# Power.net
KiCad netlist of a schematic drawn in Altium Designer
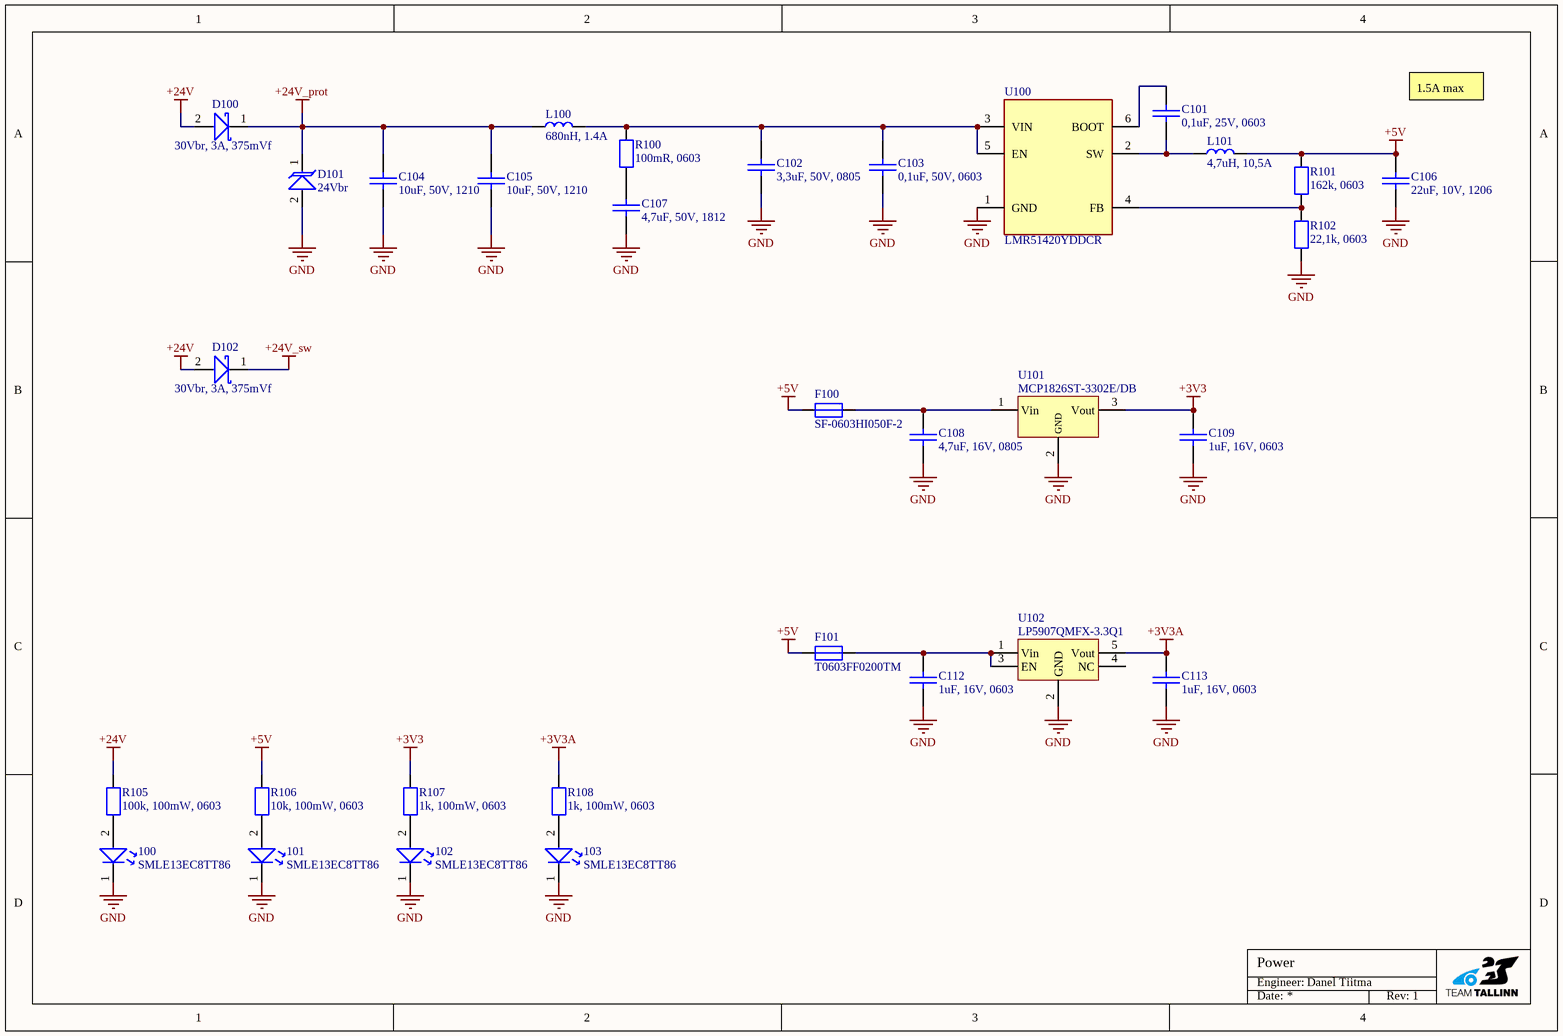
[diagram p0: Power.SchDoc]

(export (version "E")
  (design (tool "Eeschema 10.0.6"))
  (components
    (comp (ref "100")
      (value "SMLE13EC8TT86")
      (footprint "LED [0603] 1608")
      (description "Single Color LED, Green, Colorless Transparent, 1.2mm")
      (libsource (lib "Formula Student Team Tallinn (Estonia)") (part "Diode LED"))
    )
    (comp (ref "101")
      (value "SMLE13EC8TT86")
      (footprint "LED [0603] 1608")
      (description "Single Color LED, Green, Colorless Transparent, 1.2mm")
      (libsource (lib "Formula Student Team Tallinn (Estonia)") (part "Diode LED"))
    )
    (comp (ref "102")
      (value "SMLE13EC8TT86")
      (footprint "LED [0603] 1608")
      (description "Single Color LED, Green, Colorless Transparent, 1.2mm")
      (libsource (lib "Formula Student Team Tallinn (Estonia)") (part "Diode LED"))
    )
    (comp (ref "103")
      (value "SMLE13EC8TT86")
      (footprint "LED [0603] 1608")
      (description "Single Color LED, Green, Colorless Transparent, 1.2mm")
      (libsource (lib "Formula Student Team Tallinn (Estonia)") (part "Diode LED"))
    )
    (comp (ref "C101")
      (value "0,1uF, 25V, 0603")
      (footprint "CAP [0603] 1608")
      (description "Default capacitor part")
      (libsource (lib "Formula Student Team Tallinn (Estonia)") (part "Capacitor"))
    )
    (comp (ref "C102")
      (value "3,3uF, 50V, 0805")
      (footprint "CAP [0805] 2012")
      (fields
        (field (name "MANUFACTURER") "TDK")
        (field (name "MANUFACTURER PART NUMBER") "C2012X5R1H335K125AB")
      )
      (libsource (lib "Formula Student Team Tallinn (Estonia)") (part "Capacitor"))
    )
    (comp (ref "C103")
      (value "0,1uF, 50V, 0603")
      (footprint "CAP [0603] 1608")
      (description "Default capacitor part")
      (libsource (lib "Formula Student Team Tallinn (Estonia)") (part "Capacitor"))
    )
    (comp (ref "C104")
      (value "10uF, 50V, 1210")
      (footprint "CAP [1210] 3225")
      (fields
        (field (name "MANUFACTURER PART NUMBER") "C3225X7R1H106M250AC")
        (field (name "MANUFACTURER") "TDK")
      )
      (libsource (lib "Formula Student Team Tallinn (Estonia)") (part "Capacitor"))
    )
    (comp (ref "C105")
      (value "10uF, 50V, 1210")
      (footprint "CAP [1210] 3225")
      (fields
        (field (name "MANUFACTURER PART NUMBER") "C3225X7R1H106M250AC")
        (field (name "MANUFACTURER") "TDK")
      )
      (libsource (lib "Formula Student Team Tallinn (Estonia)") (part "Capacitor"))
    )
    (comp (ref "C106")
      (value "22uF, 10V, 1206")
      (footprint "CAP [1206] 3216")
      (fields
        (field (name "MANUFACTURER") "Murata")
        (field (name "MANUFACTURER PART NUMBER") "GRM31CR71A226KE15L")
      )
      (libsource (lib "Formula Student Team Tallinn (Estonia)") (part "Capacitor"))
    )
    (comp (ref "C107")
      (value "4,7uF, 50V, 1812")
      (footprint "CAP [1812] 4532")
      (fields
        (field (name "MANUFACTURER PART NUMBER") "C4532X7S2A475K230KB")
        (field (name "MANUFACTURER") "TDK")
      )
      (libsource (lib "Formula Student Team Tallinn (Estonia)") (part "Capacitor"))
    )
    (comp (ref "C108")
      (value "4,7uF, 16V, 0805")
      (footprint "CAP [0805] 2012")
      (description "Default capacitor part")
      (libsource (lib "Formula Student Team Tallinn (Estonia)") (part "Capacitor"))
    )
    (comp (ref "C109")
      (value "1uF, 16V, 0603")
      (footprint "CAP [0603] 1608")
      (description "Default capacitor part")
      (libsource (lib "Formula Student Team Tallinn (Estonia)") (part "Capacitor"))
    )
    (comp (ref "C112")
      (value "1uF, 16V, 0603")
      (footprint "CAP [0603] 1608")
      (description "Default capacitor part")
      (libsource (lib "Formula Student Team Tallinn (Estonia)") (part "Capacitor"))
    )
    (comp (ref "C113")
      (value "1uF, 16V, 0603")
      (footprint "CAP [0603] 1608")
      (description "Default capacitor part")
      (libsource (lib "Formula Student Team Tallinn (Estonia)") (part "Capacitor"))
    )
    (comp (ref "D100")
      (value "30Vbr, 3A, 375mVf")
      (footprint "SOD-128")
      (description "Rectifier Diode, Schottky, 1 Phase, 1 Element, 2A, Silicon")
      (fields (field (name "MANUFACTURER PART NUMBER") "PMEG3020EP,115"))
      (libsource (lib "Formula Student Team Tallinn (Estonia)") (part "Diode Shottky"))
    )
    (comp (ref "D101")
      (value "24Vbr")
      (footprint "SOD-123W")
      (description "Trans Voltage Suppressor Diode, 400W, 24V V(RWM), Unidirectional, 1 Element, Silicon")
      (fields
        (field (name "MANUFACTURER PART NUMBER") "PTVS24VS1UR,115")
        (field (name "MANUFACTURER") "Nexperia")
      )
      (libsource (lib "Formula Student Team Tallinn (Estonia)") (part "Diode TVS"))
    )
    (comp (ref "D102")
      (value "30Vbr, 3A, 375mVf")
      (footprint "SOD-128")
      (description "Rectifier Diode, Schottky, 1 Phase, 1 Element, 2A, Silicon")
      (fields (field (name "MANUFACTURER PART NUMBER") "PMEG3020EP,115"))
      (libsource (lib "Formula Student Team Tallinn (Estonia)") (part "Diode Shottky"))
    )
    (comp (ref "F100")
      (value "SF-0603HI050F-2")
      (footprint "FUSE [0603] 1608")
      (description "Electric Fuse, 0.5A, 35VAC, 65VDC, 50A (IR), Surface Mount")
      (fields (field (name "MANUFACTURER") "Bourns"))
      (libsource (lib "Formula Student Team Tallinn (Estonia)") (part "Fuse"))
    )
    (comp (ref "F101")
      (value "T0603FF0200TM")
      (footprint "FUSE [0603] 1608")
      (description "Fuse, Very Fast Act, 0.2A, 65VDC, 0603 Rohs Compliant: Yes")
      (libsource (lib "Formula Student Team Tallinn (Estonia)") (part "Fuse"))
    )
    (comp (ref "L100")
      (value "680nH, 1.4A")
      (footprint "PFL1609-681MEW-Footprint-1")
      (description "General Purpose Inductor, 0.68uH, 20%, 1 Element, Composite-Core, SMD, 0603")
      (fields
        (field (name "MANUFACTURER") "Coilcraft")
        (field (name "MANUFACTURER PART NUMBER") "PFL1609-681MEW")
      )
      (libsource (lib "Formula Student Team Tallinn (Estonia)") (part "Inductor"))
    )
    (comp (ref "L101")
      (value "4,7uH, 10,5A")
      (footprint "FP-XAL6060-472MEC-MFG")
      (description "General Purpose Inductor, 4.7uH, 20%, 1 Element, Composite-Core, SMD, 2625")
      (fields
        (field (name "MANUFACTURER") "Coilcraft")
        (field (name "MANUFACTURER PART NUMBER") "XAL6060-472MEC")
      )
      (libsource (lib "Formula Student Team Tallinn (Estonia)") (part "Inductor"))
    )
    (comp (ref "R100")
      (value "100mR, 0603")
      (footprint "RES [0603] 1608")
      (description "Standard resistor part")
      (libsource (lib "Formula Student Team Tallinn (Estonia)") (part "Resistor"))
    )
    (comp (ref "R101")
      (value "162k, 0603")
      (footprint "RES [0603] 1608")
      (description "Standard resistor part")
      (libsource (lib "Formula Student Team Tallinn (Estonia)") (part "Resistor"))
    )
    (comp (ref "R102")
      (value "22,1k, 0603")
      (footprint "RES [0603] 1608")
      (description "Standard resistor part")
      (libsource (lib "Formula Student Team Tallinn (Estonia)") (part "Resistor"))
    )
    (comp (ref "R105")
      (value "100k, 100mW, 0603")
      (footprint "RES [0603] 1608")
      (description "Standard resistor part")
      (libsource (lib "Formula Student Team Tallinn (Estonia)") (part "Resistor"))
    )
    (comp (ref "R106")
      (value "10k, 100mW, 0603")
      (footprint "RES [0603] 1608")
      (description "Standard resistor part")
      (libsource (lib "Formula Student Team Tallinn (Estonia)") (part "Resistor"))
    )
    (comp (ref "R107")
      (value "1k, 100mW, 0603")
      (footprint "RES [0603] 1608")
      (description "Standard resistor part")
      (libsource (lib "Formula Student Team Tallinn (Estonia)") (part "Resistor"))
    )
    (comp (ref "R108")
      (value "1k, 100mW, 0603")
      (footprint "RES [0603] 1608")
      (description "Standard resistor part")
      (libsource (lib "Formula Student Team Tallinn (Estonia)") (part "Resistor"))
    )
    (comp (ref "U100")
      (value "LMR51420YDDCR")
      (footprint "SOT23-6")
      (fields (field (name "MANUFACTURER") "Texas Instruments"))
      (libsource (lib "Formula Student Team Tallinn (Estonia)") (part "LMR51420XFDDCR-Symbol-1"))
    )
    (comp (ref "U101")
      (value "MCP1826ST-3302E/DB")
      (footprint "SOT223")
      (description "Fixed Positive LDO Regulator, 3.3V, 0.4V Dropout, CMOS, PDSO3")
      (fields
        (field (name "MANUFACTURER") "Microchip")
        (field (name "MANUFACTURER PART NUMBER") "579-MCP1826ST3302EDB")
      )
      (libsource (lib "Formula Student Team Tallinn (Estonia)") (part "SIP-3 DCDC"))
    )
    (comp (ref "U102")
      (value "LP5907QMFX-3.3Q1")
      (footprint "SOT23-5")
      (description "Fixed Positive LDO Regulator, 3.3V, 0.25V Dropout, PDSO5")
      (fields (field (name "MANUFACTURER") "Texas Instruments"))
      (libsource (lib "Formula Student Team Tallinn (Estonia)") (part "LDO 5-pin"))
    )
  )
  (nets
    (net (code "1") (name "+3V3") (class "Default")
      (node (ref "C109") (pin "1") (pinfunction "1_1") (pintype "passive"))
      (node (ref "R107") (pin "2") (pinfunction "2_2") (pintype "passive"))
      (node (ref "U101") (pin "3") (pinfunction "Vout_3") (pintype "passive"))
    )
    (net (code "2") (name "+3V3A") (class "Default")
      (node (ref "C113") (pin "1") (pinfunction "1_1") (pintype "passive"))
      (node (ref "R108") (pin "2") (pinfunction "2_2") (pintype "passive"))
      (node (ref "U102") (pin "5") (pinfunction "Vout_5") (pintype "passive"))
    )
    (net (code "3") (name "+5V") (class "Default")
      (node (ref "C106") (pin "2") (pinfunction "2_2") (pintype "passive"))
      (node (ref "F100") (pin "1") (pinfunction "1_1") (pintype "passive"))
      (node (ref "F101") (pin "2") (pinfunction "2_2") (pintype "passive"))
      (node (ref "L101") (pin "2") (pinfunction "2_2") (pintype "passive"))
      (node (ref "R101") (pin "1") (pinfunction "1_1") (pintype "passive"))
      (node (ref "R106") (pin "2") (pinfunction "2_2") (pintype "passive"))
    )
    (net (code "4") (name "+24V") (class "Default")
      (node (ref "D100") (pin "2") (pinfunction "A_2") (pintype "passive"))
      (node (ref "D102") (pin "2") (pinfunction "A_2") (pintype "passive"))
      (node (ref "R105") (pin "2") (pinfunction "2_2") (pintype "passive"))
    )
    (net (code "5") (name "+24V_prot") (class "Default")
      (node (ref "C104") (pin "1") (pinfunction "1_1") (pintype "passive"))
      (node (ref "C105") (pin "1") (pinfunction "1_1") (pintype "passive"))
      (node (ref "D100") (pin "1") (pinfunction "K_1") (pintype "passive"))
      (node (ref "D101") (pin "1") (pinfunction "K_1") (pintype "passive"))
      (node (ref "L100") (pin "1") (pinfunction "1_1") (pintype "passive"))
    )
    (net (code "6") (name "+24V_sw") (class "Default")
      (node (ref "D102") (pin "1") (pinfunction "K_1") (pintype "passive"))
    )
    (net (code "7") (name "GND") (class "Default")
      (node (ref "100") (pin "1") (pinfunction "1_1") (pintype "passive"))
      (node (ref "101") (pin "1") (pinfunction "1_1") (pintype "passive"))
      (node (ref "102") (pin "1") (pinfunction "1_1") (pintype "passive"))
      (node (ref "103") (pin "1") (pinfunction "1_1") (pintype "passive"))
      (node (ref "C102") (pin "1") (pinfunction "1_1") (pintype "passive"))
      (node (ref "C103") (pin "1") (pinfunction "1_1") (pintype "passive"))
      (node (ref "C104") (pin "2") (pinfunction "2_2") (pintype "passive"))
      (node (ref "C105") (pin "2") (pinfunction "2_2") (pintype "passive"))
      (node (ref "C106") (pin "1") (pinfunction "1_1") (pintype "passive"))
      (node (ref "C107") (pin "2") (pinfunction "2_2") (pintype "passive"))
      (node (ref "C108") (pin "2") (pinfunction "2_2") (pintype "passive"))
      (node (ref "C109") (pin "2") (pinfunction "2_2") (pintype "passive"))
      (node (ref "C112") (pin "2") (pinfunction "2_2") (pintype "passive"))
      (node (ref "C113") (pin "2") (pinfunction "2_2") (pintype "passive"))
      (node (ref "D101") (pin "2") (pinfunction "A_2") (pintype "passive"))
      (node (ref "R102") (pin "2") (pinfunction "2_2") (pintype "passive"))
      (node (ref "U100") (pin "1") (pinfunction "GND_1") (pintype "passive"))
      (node (ref "U101") (pin "2") (pinfunction "GND_2") (pintype "passive"))
      (node (ref "U102") (pin "2") (pinfunction "GND_2") (pintype "passive"))
    )
    (net (code "8") (name "Net-(100-Pad2)") (class "Default")
      (node (ref "100") (pin "2") (pinfunction "2_2") (pintype "passive"))
      (node (ref "R105") (pin "1") (pinfunction "1_1") (pintype "passive"))
    )
    (net (code "9") (name "Net-(101-Pad2)") (class "Default")
      (node (ref "101") (pin "2") (pinfunction "2_2") (pintype "passive"))
      (node (ref "R106") (pin "1") (pinfunction "1_1") (pintype "passive"))
    )
    (net (code "10") (name "Net-(102-Pad2)") (class "Default")
      (node (ref "102") (pin "2") (pinfunction "2_2") (pintype "passive"))
      (node (ref "R107") (pin "1") (pinfunction "1_1") (pintype "passive"))
    )
    (net (code "11") (name "Net-(103-Pad2)") (class "Default")
      (node (ref "103") (pin "2") (pinfunction "2_2") (pintype "passive"))
      (node (ref "R108") (pin "1") (pinfunction "1_1") (pintype "passive"))
    )
    (net (code "12") (name "Net-(C107-Pad1)") (class "Default")
      (node (ref "C107") (pin "1") (pinfunction "1_1") (pintype "passive"))
      (node (ref "R100") (pin "2") (pinfunction "2_2") (pintype "passive"))
    )
    (net (code "13") (name "Net-(U100-BOOT)") (class "Default")
      (node (ref "C101") (pin "2") (pinfunction "2_2") (pintype "passive"))
      (node (ref "U100") (pin "6") (pinfunction "BOOT_6") (pintype "passive"))
    )
    (net (code "14") (name "Net-(U100-EN)") (class "Default")
      (node (ref "C102") (pin "2") (pinfunction "2_2") (pintype "passive"))
      (node (ref "C103") (pin "2") (pinfunction "2_2") (pintype "passive"))
      (node (ref "L100") (pin "2") (pinfunction "2_2") (pintype "passive"))
      (node (ref "R100") (pin "1") (pinfunction "1_1") (pintype "passive"))
      (node (ref "U100") (pin "3") (pinfunction "VIN_3") (pintype "passive"))
      (node (ref "U100") (pin "5") (pinfunction "EN_5") (pintype "passive"))
    )
    (net (code "15") (name "Net-(U100-FB)") (class "Default")
      (node (ref "R101") (pin "2") (pinfunction "2_2") (pintype "passive"))
      (node (ref "R102") (pin "1") (pinfunction "1_1") (pintype "passive"))
      (node (ref "U100") (pin "4") (pinfunction "FB_4") (pintype "passive"))
    )
    (net (code "16") (name "Net-(U100-SW)") (class "Default")
      (node (ref "C101") (pin "1") (pinfunction "1_1") (pintype "passive"))
      (node (ref "L101") (pin "1") (pinfunction "1_1") (pintype "passive"))
      (node (ref "U100") (pin "2") (pinfunction "SW_2") (pintype "passive"))
    )
    (net (code "17") (name "Net-(U101-Vin)") (class "Default")
      (node (ref "C108") (pin "1") (pinfunction "1_1") (pintype "passive"))
      (node (ref "F100") (pin "2") (pinfunction "2_2") (pintype "passive"))
      (node (ref "U101") (pin "1") (pinfunction "Vin_1") (pintype "passive"))
    )
    (net (code "18") (name "Net-(U102-EN)") (class "Default")
      (node (ref "C112") (pin "1") (pinfunction "1_1") (pintype "passive"))
      (node (ref "F101") (pin "1") (pinfunction "1_1") (pintype "passive"))
      (node (ref "U102") (pin "1") (pinfunction "Vin_1") (pintype "passive"))
      (node (ref "U102") (pin "3") (pinfunction "EN_3") (pintype "passive"))
    )
    (net (code "19") (name "unconnected-(U102-NC-Pad4)") (class "Default")
      (node (ref "U102") (pin "4") (pinfunction "NC_4") (pintype "passive"))
    )
  )
)
